# Scheda_motori_L298.net
KiCad netlist of a schematic drawn in EAGLE
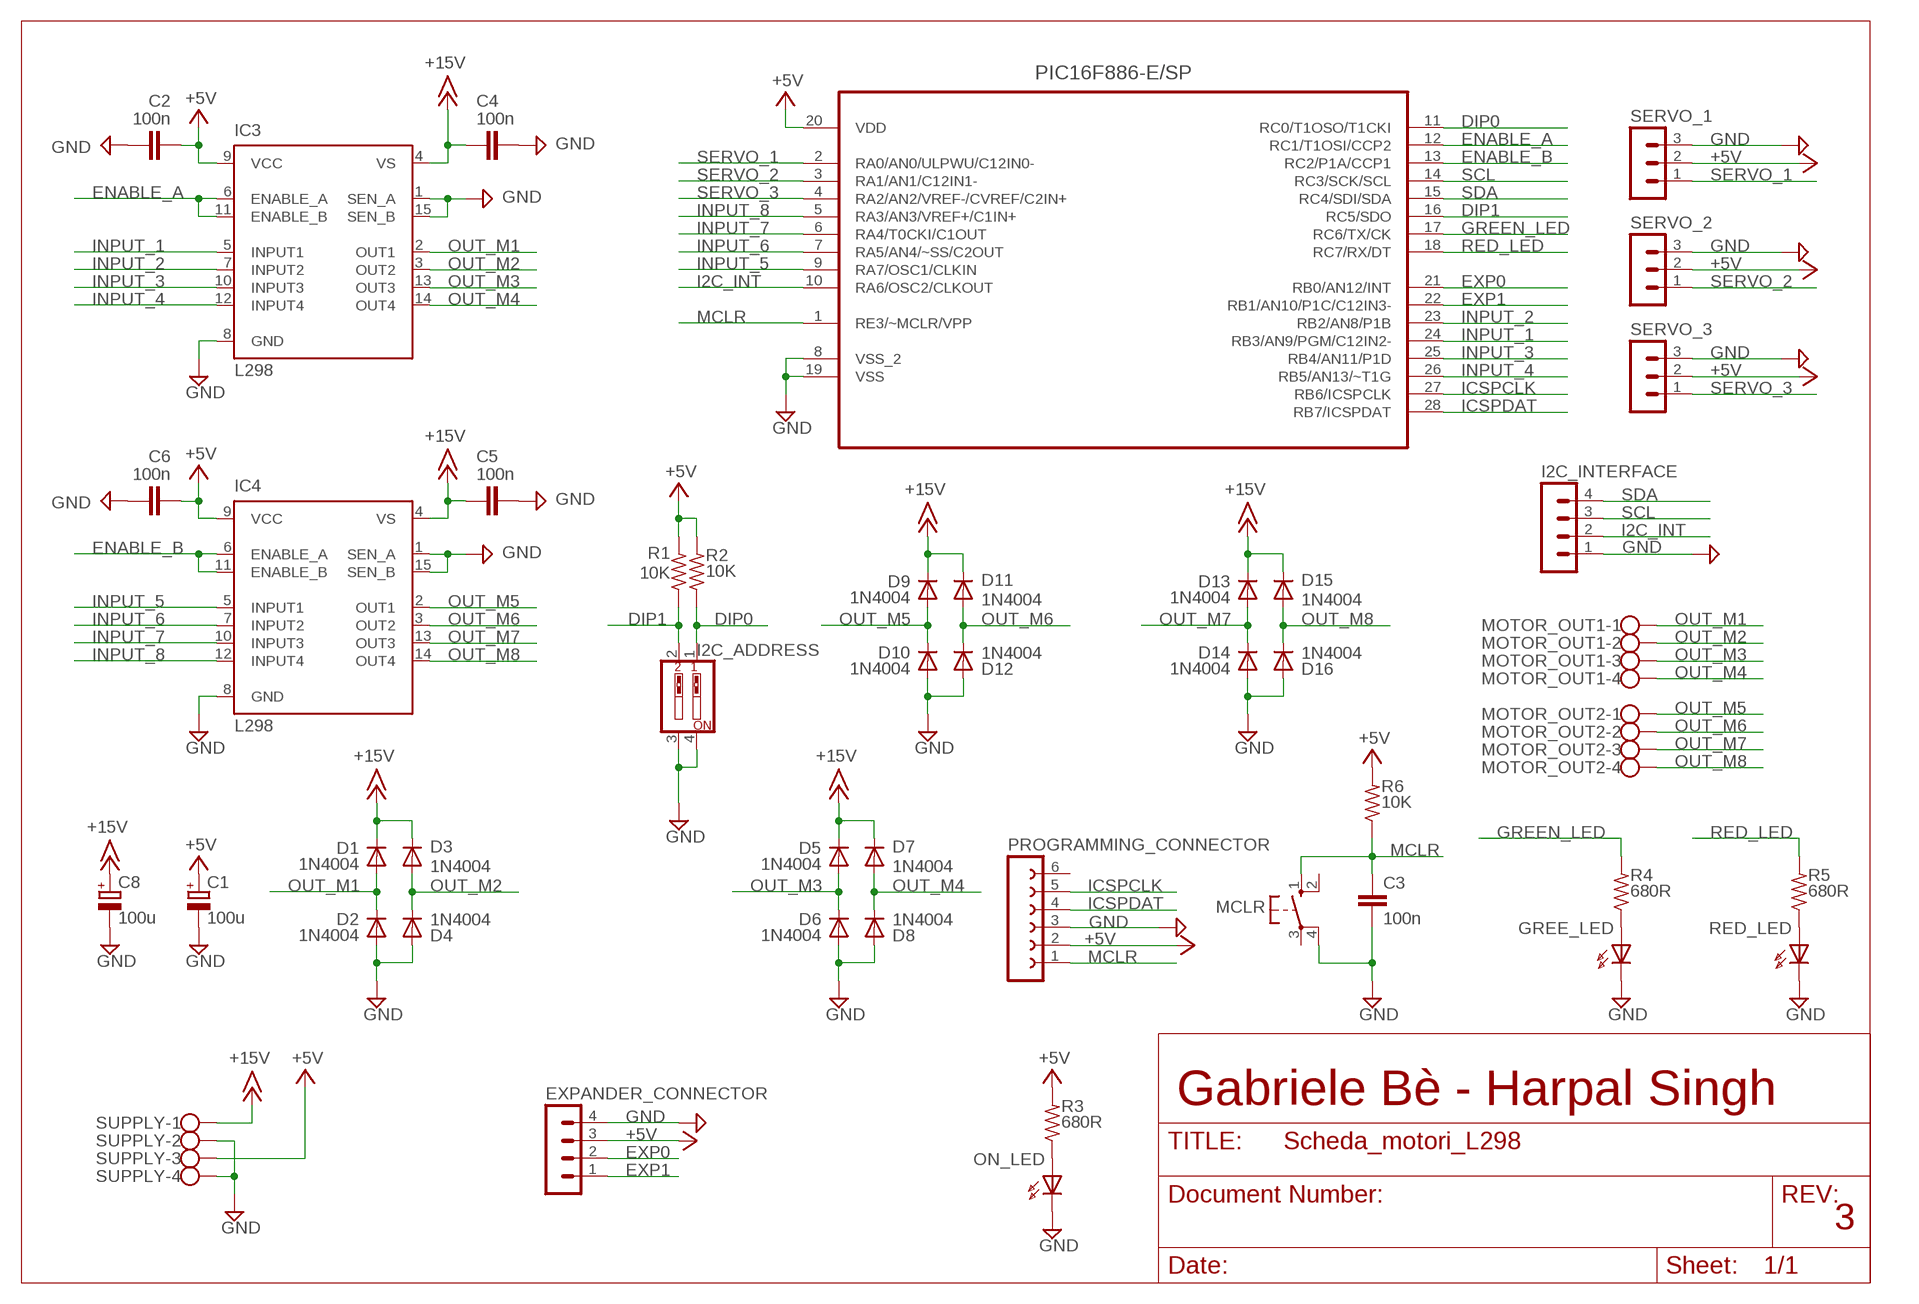
[diagram p0: schematic, sheet 1]

(export (version "E")
  (design (tool "Eeschema 10.0.6"))
  (components
    (comp (ref "C1")
      (value "100u")
      (footprint "eagle-import:E2,5-7")
      (libsource (lib "eagle-import") (part "CPOL-EUE2.5-7"))
    )
    (comp (ref "C2")
      (value "100n")
      (footprint "eagle-import:C050-024X044")
      (libsource (lib "eagle-import") (part "C-EU050-024X044"))
    )
    (comp (ref "C3")
      (value "100n")
      (footprint "eagle-import:C050-024X044")
      (libsource (lib "eagle-import") (part "C-EU050-024X044"))
    )
    (comp (ref "C4")
      (value "100n")
      (footprint "eagle-import:C050-024X044")
      (libsource (lib "eagle-import") (part "C-EU050-024X044"))
    )
    (comp (ref "C5")
      (value "100n")
      (footprint "eagle-import:C050-024X044")
      (libsource (lib "eagle-import") (part "C-EU050-024X044"))
    )
    (comp (ref "C6")
      (value "100n")
      (footprint "eagle-import:C050-024X044")
      (libsource (lib "eagle-import") (part "C-EU050-024X044"))
    )
    (comp (ref "C8")
      (value "100u")
      (footprint "eagle-import:E2,5-7")
      (libsource (lib "eagle-import") (part "CPOL-EUE2.5-7"))
    )
    (comp (ref "D1")
      (value "1N4004")
      (footprint "eagle-import:DO41-10")
      (libsource (lib "eagle-import") (part "1N4004"))
    )
    (comp (ref "D2")
      (value "1N4004")
      (footprint "eagle-import:DO41-10")
      (libsource (lib "eagle-import") (part "1N4004"))
    )
    (comp (ref "D3")
      (value "1N4004")
      (footprint "eagle-import:DO41-10")
      (libsource (lib "eagle-import") (part "1N4004"))
    )
    (comp (ref "D4")
      (value "1N4004")
      (footprint "eagle-import:DO41-10")
      (libsource (lib "eagle-import") (part "1N4004"))
    )
    (comp (ref "D5")
      (value "1N4004")
      (footprint "eagle-import:DO41-10")
      (libsource (lib "eagle-import") (part "1N4004"))
    )
    (comp (ref "D6")
      (value "1N4004")
      (footprint "eagle-import:DO41-10")
      (libsource (lib "eagle-import") (part "1N4004"))
    )
    (comp (ref "D7")
      (value "1N4004")
      (footprint "eagle-import:DO41-10")
      (libsource (lib "eagle-import") (part "1N4004"))
    )
    (comp (ref "D8")
      (value "1N4004")
      (footprint "eagle-import:DO41-10")
      (libsource (lib "eagle-import") (part "1N4004"))
    )
    (comp (ref "D9")
      (value "1N4004")
      (footprint "eagle-import:DO41-10")
      (libsource (lib "eagle-import") (part "1N4004"))
    )
    (comp (ref "D10")
      (value "1N4004")
      (footprint "eagle-import:DO41-10")
      (libsource (lib "eagle-import") (part "1N4004"))
    )
    (comp (ref "D11")
      (value "1N4004")
      (footprint "eagle-import:DO41-10")
      (libsource (lib "eagle-import") (part "1N4004"))
    )
    (comp (ref "D12")
      (value "1N4004")
      (footprint "eagle-import:DO41-10")
      (libsource (lib "eagle-import") (part "1N4004"))
    )
    (comp (ref "D13")
      (value "1N4004")
      (footprint "eagle-import:DO41-10")
      (libsource (lib "eagle-import") (part "1N4004"))
    )
    (comp (ref "D14")
      (value "1N4004")
      (footprint "eagle-import:DO41-10")
      (libsource (lib "eagle-import") (part "1N4004"))
    )
    (comp (ref "D15")
      (value "1N4004")
      (footprint "eagle-import:DO41-10")
      (libsource (lib "eagle-import") (part "1N4004"))
    )
    (comp (ref "D16")
      (value "1N4004")
      (footprint "eagle-import:DO41-10")
      (libsource (lib "eagle-import") (part "1N4004"))
    )
    (comp (ref "EXPANDER_CONNECTOR")
      (value "MA04-1")
      (footprint "eagle-import:MA04-1")
      (libsource (lib "eagle-import") (part "MA04-1"))
    )
    (comp (ref "GREE_LED")
      (value "HLMP6")
      (footprint "eagle-import:HLMP6")
      (fields (field (name "MF") "AGILENT TECHNOLOGIES") (field (name "MPN") "HLMP-6500"))
      (libsource (lib "eagle-import") (part "HLMP6"))
    )
    (comp (ref "I2C_ADDRESS")
      (value "SW_DIP-2")
      (footprint "eagle-import:EDG-02")
      (libsource (lib "eagle-import") (part "SW_DIP-2"))
    )
    (comp (ref "I2C_INTERFACE")
      (value "MA04-1")
      (footprint "eagle-import:MA04-1")
      (libsource (lib "eagle-import") (part "MA04-1"))
    )
    (comp (ref "IC3")
      (value "L298")
      (footprint "eagle-import:MULTIWATT-15")
      (libsource (lib "eagle-import") (part "L298"))
    )
    (comp (ref "IC4")
      (value "L298")
      (footprint "eagle-import:MULTIWATT-15")
      (libsource (lib "eagle-import") (part "L298"))
    )
    (comp (ref "MCLR")
      (value "10-XX")
      (footprint "eagle-import:B3F-10XX")
      (libsource (lib "eagle-import") (part "10-XX"))
    )
    (comp (ref "MOTOR_OUT1")
      (value "W237-4")
      (footprint "eagle-import:W237-4")
      (libsource (lib "eagle-import") (part "W237-4"))
    )
    (comp (ref "MOTOR_OUT2")
      (value "W237-4")
      (footprint "eagle-import:W237-4")
      (libsource (lib "eagle-import") (part "W237-4"))
    )
    (comp (ref "ON_LED")
      (value "HLMP6")
      (footprint "eagle-import:HLMP6")
      (fields (field (name "MF") "AGILENT TECHNOLOGIES") (field (name "MPN") "HLMP-6500"))
      (libsource (lib "eagle-import") (part "HLMP6"))
    )
    (comp (ref "PROGRAMMING_CONNECTOR")
      (value "FE06-1")
      (footprint "eagle-import:FE06")
      (libsource (lib "eagle-import") (part "FE06-1"))
    )
    (comp (ref "R1")
      (value "10K")
      (footprint "eagle-import:0207_10")
      (libsource (lib "eagle-import") (part "R-US_0207/10"))
    )
    (comp (ref "R2")
      (value "10K")
      (footprint "eagle-import:0207_10")
      (libsource (lib "eagle-import") (part "R-US_0207/10"))
    )
    (comp (ref "R3")
      (value "680R")
      (footprint "eagle-import:0207_10")
      (libsource (lib "eagle-import") (part "R-US_0207/10"))
    )
    (comp (ref "R4")
      (value "680R")
      (footprint "eagle-import:0207_10")
      (libsource (lib "eagle-import") (part "R-US_0207/10"))
    )
    (comp (ref "R5")
      (value "680R")
      (footprint "eagle-import:0207_10")
      (libsource (lib "eagle-import") (part "R-US_0207/10"))
    )
    (comp (ref "R6")
      (value "10K")
      (footprint "eagle-import:0207_10")
      (libsource (lib "eagle-import") (part "R-US_0207/10"))
    )
    (comp (ref "RED_LED")
      (value "HLMP6")
      (footprint "eagle-import:HLMP6")
      (fields (field (name "MF") "AGILENT TECHNOLOGIES") (field (name "MPN") "HLMP-6500"))
      (libsource (lib "eagle-import") (part "HLMP6"))
    )
    (comp (ref "SERVO_1")
      (value "MA03-1")
      (footprint "eagle-import:MA03-1")
      (libsource (lib "eagle-import") (part "MA03-1"))
    )
    (comp (ref "SERVO_2")
      (value "MA03-1")
      (footprint "eagle-import:MA03-1")
      (libsource (lib "eagle-import") (part "MA03-1"))
    )
    (comp (ref "SERVO_3")
      (value "MA03-1")
      (footprint "eagle-import:MA03-1")
      (libsource (lib "eagle-import") (part "MA03-1"))
    )
    (comp (ref "SUPPLY")
      (value "W237-4")
      (footprint "eagle-import:W237-4")
      (libsource (lib "eagle-import") (part "W237-4"))
    )
    (comp (ref "U$1")
      (value "PIC16F886-E/SP")
      (footprint "eagle-import:DIP254P762X508-28")
      (libsource (lib "eagle-import") (part "PIC16F886-E/SP"))
    )
  )
  (nets
    (net (code "1") (name "+5V") (class "Default")
      (node (ref "C1") (pin "+") (pinfunction "+_+") (pintype "passive"))
      (node (ref "C2") (pin "2") (pinfunction "2_2") (pintype "passive"))
      (node (ref "C6") (pin "2") (pinfunction "2_2") (pintype "passive"))
      (node (ref "EXPANDER_CONNECTOR") (pin "3") (pinfunction "3_3") (pintype "passive"))
      (node (ref "IC3") (pin "9") (pinfunction "VCC_9") (pintype "power_in"))
      (node (ref "IC4") (pin "9") (pinfunction "VCC_9") (pintype "power_in"))
      (node (ref "PROGRAMMING_CONNECTOR") (pin "2") (pinfunction "2_2") (pintype "passive"))
      (node (ref "R1") (pin "2") (pinfunction "2_2") (pintype "passive"))
      (node (ref "R2") (pin "2") (pinfunction "2_2") (pintype "passive"))
      (node (ref "R3") (pin "2") (pinfunction "2_2") (pintype "passive"))
      (node (ref "R6") (pin "2") (pinfunction "2_2") (pintype "passive"))
      (node (ref "SERVO_1") (pin "2") (pinfunction "2_2") (pintype "passive"))
      (node (ref "SERVO_2") (pin "2") (pinfunction "2_2") (pintype "passive"))
      (node (ref "SERVO_3") (pin "2") (pinfunction "2_2") (pintype "passive"))
      (node (ref "SUPPLY") (pin "3") (pinfunction "KL_3") (pintype "passive"))
      (node (ref "U$1") (pin "20") (pinfunction "VDD_20") (pintype "power_in"))
    )
    (net (code "2") (name "+15V") (class "Default")
      (node (ref "C4") (pin "1") (pinfunction "1_1") (pintype "passive"))
      (node (ref "C5") (pin "1") (pinfunction "1_1") (pintype "passive"))
      (node (ref "C8") (pin "+") (pinfunction "+_+") (pintype "passive"))
      (node (ref "D1") (pin "C") (pinfunction "C_C") (pintype "passive"))
      (node (ref "D11") (pin "C") (pinfunction "C_C") (pintype "passive"))
      (node (ref "D13") (pin "C") (pinfunction "C_C") (pintype "passive"))
      (node (ref "D15") (pin "C") (pinfunction "C_C") (pintype "passive"))
      (node (ref "D3") (pin "C") (pinfunction "C_C") (pintype "passive"))
      (node (ref "D5") (pin "C") (pinfunction "C_C") (pintype "passive"))
      (node (ref "D7") (pin "C") (pinfunction "C_C") (pintype "passive"))
      (node (ref "D9") (pin "C") (pinfunction "C_C") (pintype "passive"))
      (node (ref "IC3") (pin "4") (pinfunction "VS_4") (pintype "power_in"))
      (node (ref "IC4") (pin "4") (pinfunction "VS_4") (pintype "power_in"))
      (node (ref "SUPPLY") (pin "1") (pinfunction "KL_1") (pintype "passive"))
    )
    (net (code "3") (name "/DIP0") (class "Default")
      (node (ref "I2C_ADDRESS") (pin "1") (pinfunction "1_1") (pintype "passive"))
      (node (ref "R2") (pin "1") (pinfunction "1_1") (pintype "passive"))
      (node (ref "U$1") (pin "11") (pinfunction "RC0/T1OSO/T1CKI_11") (pintype "bidirectional"))
    )
    (net (code "4") (name "/DIP1") (class "Default")
      (node (ref "I2C_ADDRESS") (pin "2") (pinfunction "2_2") (pintype "passive"))
      (node (ref "R1") (pin "1") (pinfunction "1_1") (pintype "passive"))
      (node (ref "U$1") (pin "16") (pinfunction "RC5/SDO_16") (pintype "bidirectional"))
    )
    (net (code "5") (name "/ENABLE_A") (class "Default")
      (node (ref "IC3") (pin "11") (pinfunction "ENABLE_B_11") (pintype "input"))
      (node (ref "IC3") (pin "6") (pinfunction "ENABLE_A_6") (pintype "input"))
      (node (ref "U$1") (pin "12") (pinfunction "RC1/T1OSI/CCP2_12") (pintype "bidirectional"))
    )
    (net (code "6") (name "/ENABLE_B") (class "Default")
      (node (ref "IC4") (pin "11") (pinfunction "ENABLE_B_11") (pintype "input"))
      (node (ref "IC4") (pin "6") (pinfunction "ENABLE_A_6") (pintype "input"))
      (node (ref "U$1") (pin "13") (pinfunction "RC2/P1A/CCP1_13") (pintype "bidirectional"))
    )
    (net (code "7") (name "/EXP0") (class "Default")
      (node (ref "EXPANDER_CONNECTOR") (pin "2") (pinfunction "2_2") (pintype "passive"))
      (node (ref "U$1") (pin "21") (pinfunction "RB0/AN12/INT_21") (pintype "bidirectional"))
    )
    (net (code "8") (name "/EXP1") (class "Default")
      (node (ref "EXPANDER_CONNECTOR") (pin "1") (pinfunction "1_1") (pintype "passive"))
      (node (ref "U$1") (pin "22") (pinfunction "RB1/AN10/P1C/C12IN3-_22") (pintype "bidirectional"))
    )
    (net (code "9") (name "/GREEN_LED") (class "Default")
      (node (ref "R4") (pin "2") (pinfunction "2_2") (pintype "passive"))
      (node (ref "U$1") (pin "17") (pinfunction "RC6/TX/CK_17") (pintype "bidirectional"))
    )
    (net (code "10") (name "/I2C_INT") (class "Default")
      (node (ref "I2C_INTERFACE") (pin "2") (pinfunction "2_2") (pintype "passive"))
      (node (ref "U$1") (pin "10") (pinfunction "RA6/OSC2/CLKOUT_10") (pintype "bidirectional"))
    )
    (net (code "11") (name "/ICSPCLK") (class "Default")
      (node (ref "PROGRAMMING_CONNECTOR") (pin "5") (pinfunction "5_5") (pintype "passive"))
      (node (ref "U$1") (pin "27") (pinfunction "RB6/ICSPCLK_27") (pintype "bidirectional"))
    )
    (net (code "12") (name "/ICSPDAT") (class "Default")
      (node (ref "PROGRAMMING_CONNECTOR") (pin "4") (pinfunction "4_4") (pintype "passive"))
      (node (ref "U$1") (pin "28") (pinfunction "RB7/ICSPDAT_28") (pintype "bidirectional"))
    )
    (net (code "13") (name "/INPUT_1") (class "Default")
      (node (ref "IC3") (pin "5") (pinfunction "INPUT1_5") (pintype "input"))
      (node (ref "U$1") (pin "24") (pinfunction "RB3/AN9/PGM/C12IN2-_24") (pintype "bidirectional"))
    )
    (net (code "14") (name "/INPUT_2") (class "Default")
      (node (ref "IC3") (pin "7") (pinfunction "INPUT2_7") (pintype "input"))
      (node (ref "U$1") (pin "23") (pinfunction "RB2/AN8/P1B_23") (pintype "bidirectional"))
    )
    (net (code "15") (name "/INPUT_3") (class "Default")
      (node (ref "IC3") (pin "10") (pinfunction "INPUT3_10") (pintype "input"))
      (node (ref "U$1") (pin "25") (pinfunction "RB4/AN11/P1D_25") (pintype "bidirectional"))
    )
    (net (code "16") (name "/INPUT_4") (class "Default")
      (node (ref "IC3") (pin "12") (pinfunction "INPUT4_12") (pintype "input"))
      (node (ref "U$1") (pin "26") (pinfunction "RB5/AN13/~{T1G}_26") (pintype "bidirectional"))
    )
    (net (code "17") (name "/INPUT_5") (class "Default")
      (node (ref "IC4") (pin "5") (pinfunction "INPUT1_5") (pintype "input"))
      (node (ref "U$1") (pin "9") (pinfunction "RA7/OSC1/CLKIN_9") (pintype "bidirectional"))
    )
    (net (code "18") (name "/INPUT_6") (class "Default")
      (node (ref "IC4") (pin "7") (pinfunction "INPUT2_7") (pintype "input"))
      (node (ref "U$1") (pin "7") (pinfunction "RA5/AN4/~{SS/C2OUT}_7") (pintype "bidirectional"))
    )
    (net (code "19") (name "/INPUT_7") (class "Default")
      (node (ref "IC4") (pin "10") (pinfunction "INPUT3_10") (pintype "input"))
      (node (ref "U$1") (pin "6") (pinfunction "RA4/T0CKI/C1OUT_6") (pintype "bidirectional"))
    )
    (net (code "20") (name "/INPUT_8") (class "Default")
      (node (ref "IC4") (pin "12") (pinfunction "INPUT4_12") (pintype "input"))
      (node (ref "U$1") (pin "5") (pinfunction "RA3/AN3/VREF+/C1IN+_5") (pintype "bidirectional"))
    )
    (net (code "21") (name "/MCLR") (class "Default")
      (node (ref "C3") (pin "1") (pinfunction "1_1") (pintype "passive"))
      (node (ref "MCLR") (pin "1") (pinfunction "S_1") (pintype "passive"))
      (node (ref "PROGRAMMING_CONNECTOR") (pin "1") (pinfunction "1_1") (pintype "passive"))
      (node (ref "R6") (pin "1") (pinfunction "1_1") (pintype "passive"))
      (node (ref "U$1") (pin "1") (pinfunction "RE3/~{MCLR/VPP}_1") (pintype "input"))
    )
    (net (code "22") (name "/OUT_M1") (class "Default")
      (node (ref "D1") (pin "A") (pinfunction "A_A") (pintype "passive"))
      (node (ref "D2") (pin "C") (pinfunction "C_C") (pintype "passive"))
      (node (ref "IC3") (pin "2") (pinfunction "OUT1_2") (pintype "output"))
      (node (ref "MOTOR_OUT1") (pin "1") (pinfunction "KL_1") (pintype "passive"))
    )
    (net (code "23") (name "/OUT_M2") (class "Default")
      (node (ref "D3") (pin "A") (pinfunction "A_A") (pintype "passive"))
      (node (ref "D4") (pin "C") (pinfunction "C_C") (pintype "passive"))
      (node (ref "IC3") (pin "3") (pinfunction "OUT2_3") (pintype "output"))
      (node (ref "MOTOR_OUT1") (pin "2") (pinfunction "KL_2") (pintype "passive"))
    )
    (net (code "24") (name "/OUT_M3") (class "Default")
      (node (ref "D5") (pin "A") (pinfunction "A_A") (pintype "passive"))
      (node (ref "D6") (pin "C") (pinfunction "C_C") (pintype "passive"))
      (node (ref "IC3") (pin "13") (pinfunction "OUT3_13") (pintype "output"))
      (node (ref "MOTOR_OUT1") (pin "3") (pinfunction "KL_3") (pintype "passive"))
    )
    (net (code "25") (name "/OUT_M4") (class "Default")
      (node (ref "D7") (pin "A") (pinfunction "A_A") (pintype "passive"))
      (node (ref "D8") (pin "C") (pinfunction "C_C") (pintype "passive"))
      (node (ref "IC3") (pin "14") (pinfunction "OUT4_14") (pintype "output"))
      (node (ref "MOTOR_OUT1") (pin "4") (pinfunction "KL_4") (pintype "passive"))
    )
    (net (code "26") (name "/OUT_M5") (class "Default")
      (node (ref "D10") (pin "C") (pinfunction "C_C") (pintype "passive"))
      (node (ref "D9") (pin "A") (pinfunction "A_A") (pintype "passive"))
      (node (ref "IC4") (pin "2") (pinfunction "OUT1_2") (pintype "output"))
      (node (ref "MOTOR_OUT2") (pin "1") (pinfunction "KL_1") (pintype "passive"))
    )
    (net (code "27") (name "/OUT_M6") (class "Default")
      (node (ref "D11") (pin "A") (pinfunction "A_A") (pintype "passive"))
      (node (ref "D12") (pin "C") (pinfunction "C_C") (pintype "passive"))
      (node (ref "IC4") (pin "3") (pinfunction "OUT2_3") (pintype "output"))
      (node (ref "MOTOR_OUT2") (pin "2") (pinfunction "KL_2") (pintype "passive"))
    )
    (net (code "28") (name "/OUT_M7") (class "Default")
      (node (ref "D13") (pin "A") (pinfunction "A_A") (pintype "passive"))
      (node (ref "D14") (pin "C") (pinfunction "C_C") (pintype "passive"))
      (node (ref "IC4") (pin "13") (pinfunction "OUT3_13") (pintype "output"))
      (node (ref "MOTOR_OUT2") (pin "3") (pinfunction "KL_3") (pintype "passive"))
    )
    (net (code "29") (name "/OUT_M8") (class "Default")
      (node (ref "D15") (pin "A") (pinfunction "A_A") (pintype "passive"))
      (node (ref "D16") (pin "C") (pinfunction "C_C") (pintype "passive"))
      (node (ref "IC4") (pin "14") (pinfunction "OUT4_14") (pintype "output"))
      (node (ref "MOTOR_OUT2") (pin "4") (pinfunction "KL_4") (pintype "passive"))
    )
    (net (code "30") (name "/RED_LED") (class "Default")
      (node (ref "R5") (pin "2") (pinfunction "2_2") (pintype "passive"))
      (node (ref "U$1") (pin "18") (pinfunction "RC7/RX/DT_18") (pintype "bidirectional"))
    )
    (net (code "31") (name "/SCL") (class "Default")
      (node (ref "I2C_INTERFACE") (pin "3") (pinfunction "3_3") (pintype "passive"))
      (node (ref "U$1") (pin "14") (pinfunction "RC3/SCK/SCL_14") (pintype "bidirectional"))
    )
    (net (code "32") (name "/SDA") (class "Default")
      (node (ref "I2C_INTERFACE") (pin "4") (pinfunction "4_4") (pintype "passive"))
      (node (ref "U$1") (pin "15") (pinfunction "RC4/SDI/SDA_15") (pintype "bidirectional"))
    )
    (net (code "33") (name "/SERVO_1") (class "Default")
      (node (ref "SERVO_1") (pin "1") (pinfunction "1_1") (pintype "passive"))
      (node (ref "U$1") (pin "2") (pinfunction "RA0/AN0/ULPWU/C12IN0-_2") (pintype "bidirectional"))
    )
    (net (code "34") (name "/SERVO_2") (class "Default")
      (node (ref "SERVO_2") (pin "1") (pinfunction "1_1") (pintype "passive"))
      (node (ref "U$1") (pin "3") (pinfunction "RA1/AN1/C12IN1-_3") (pintype "bidirectional"))
    )
    (net (code "35") (name "/SERVO_3") (class "Default")
      (node (ref "SERVO_3") (pin "1") (pinfunction "1_1") (pintype "passive"))
      (node (ref "U$1") (pin "4") (pinfunction "RA2/AN2/VREF-/CVREF/C2IN+_4") (pintype "bidirectional"))
    )
    (net (code "36") (name "GND") (class "Default")
      (node (ref "C1") (pin "-") (pinfunction "-_-") (pintype "passive"))
      (node (ref "C2") (pin "1") (pinfunction "1_1") (pintype "passive"))
      (node (ref "C3") (pin "2") (pinfunction "2_2") (pintype "passive"))
      (node (ref "C4") (pin "2") (pinfunction "2_2") (pintype "passive"))
      (node (ref "C5") (pin "2") (pinfunction "2_2") (pintype "passive"))
      (node (ref "C6") (pin "1") (pinfunction "1_1") (pintype "passive"))
      (node (ref "C8") (pin "-") (pinfunction "-_-") (pintype "passive"))
      (node (ref "D10") (pin "A") (pinfunction "A_A") (pintype "passive"))
      (node (ref "D12") (pin "A") (pinfunction "A_A") (pintype "passive"))
      (node (ref "D14") (pin "A") (pinfunction "A_A") (pintype "passive"))
      (node (ref "D16") (pin "A") (pinfunction "A_A") (pintype "passive"))
      (node (ref "D2") (pin "A") (pinfunction "A_A") (pintype "passive"))
      (node (ref "D4") (pin "A") (pinfunction "A_A") (pintype "passive"))
      (node (ref "D6") (pin "A") (pinfunction "A_A") (pintype "passive"))
      (node (ref "D8") (pin "A") (pinfunction "A_A") (pintype "passive"))
      (node (ref "EXPANDER_CONNECTOR") (pin "4") (pinfunction "4_4") (pintype "passive"))
      (node (ref "GREE_LED") (pin "K") (pinfunction "K_K") (pintype "passive"))
      (node (ref "I2C_ADDRESS") (pin "3") (pinfunction "3_3") (pintype "passive"))
      (node (ref "I2C_ADDRESS") (pin "4") (pinfunction "4_4") (pintype "passive"))
      (node (ref "I2C_INTERFACE") (pin "1") (pinfunction "1_1") (pintype "passive"))
      (node (ref "IC3") (pin "1") (pinfunction "SEN_A_1") (pintype "input"))
      (node (ref "IC3") (pin "15") (pinfunction "SEN_B_15") (pintype "input"))
      (node (ref "IC3") (pin "8") (pinfunction "GND_8") (pintype "power_in"))
      (node (ref "IC4") (pin "1") (pinfunction "SEN_A_1") (pintype "input"))
      (node (ref "IC4") (pin "15") (pinfunction "SEN_B_15") (pintype "input"))
      (node (ref "IC4") (pin "8") (pinfunction "GND_8") (pintype "power_in"))
      (node (ref "MCLR") (pin "4") (pinfunction "P1_4") (pintype "passive"))
      (node (ref "ON_LED") (pin "K") (pinfunction "K_K") (pintype "passive"))
      (node (ref "PROGRAMMING_CONNECTOR") (pin "3") (pinfunction "3_3") (pintype "passive"))
      (node (ref "RED_LED") (pin "K") (pinfunction "K_K") (pintype "passive"))
      (node (ref "SERVO_1") (pin "3") (pinfunction "3_3") (pintype "passive"))
      (node (ref "SERVO_2") (pin "3") (pinfunction "3_3") (pintype "passive"))
      (node (ref "SERVO_3") (pin "3") (pinfunction "3_3") (pintype "passive"))
      (node (ref "SUPPLY") (pin "2") (pinfunction "KL_2") (pintype "passive"))
      (node (ref "SUPPLY") (pin "4") (pinfunction "KL_4") (pintype "passive"))
      (node (ref "U$1") (pin "19") (pinfunction "VSS_19") (pintype "passive"))
      (node (ref "U$1") (pin "8") (pinfunction "VSS_2_8") (pintype "passive"))
    )
    (net (code "37") (name "Net-(GREE_LED-PadA)") (class "Default")
      (node (ref "GREE_LED") (pin "A") (pinfunction "A_A") (pintype "passive"))
      (node (ref "R4") (pin "1") (pinfunction "1_1") (pintype "passive"))
    )
    (net (code "38") (name "Net-(ON_LED-PadA)") (class "Default")
      (node (ref "ON_LED") (pin "A") (pinfunction "A_A") (pintype "passive"))
      (node (ref "R3") (pin "1") (pinfunction "1_1") (pintype "passive"))
    )
    (net (code "39") (name "Net-(R5-Pad1)") (class "Default")
      (node (ref "R5") (pin "1") (pinfunction "1_1") (pintype "passive"))
      (node (ref "RED_LED") (pin "A") (pinfunction "A_A") (pintype "passive"))
    )
    (net (code "40") (name "unconnected-(MCLR-P-Pad3)") (class "Default")
      (node (ref "MCLR") (pin "3") (pinfunction "P_3") (pintype "passive"))
    )
    (net (code "41") (name "unconnected-(MCLR-S1-Pad2)") (class "Default")
      (node (ref "MCLR") (pin "2") (pinfunction "S1_2") (pintype "passive"))
    )
    (net (code "42") (name "unconnected-(PROGRAMMING_CONNECTOR-Pad6)") (class "Default")
      (node (ref "PROGRAMMING_CONNECTOR") (pin "6") (pinfunction "6_6") (pintype "passive"))
    )
  )
)
